# Sheet1.net
KiCad netlist of a schematic drawn in Altium Designer
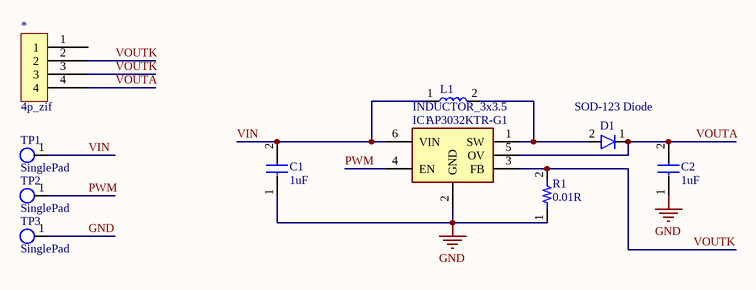
[diagram p0: Sheet1.SchDoc]

(export (version "E")
  (design (tool "Eeschema 10.0.6"))
  (components
    (comp (ref "*")
      (value "4p_zif")
      (footprint "4p_smd_zif")
      (libsource (lib "CONNECTORS AND MODULES") (part "4p_zif"))
    )
    (comp (ref "C1")
      (value "1uF")
      (footprint "0603 Capacitor")
      (description "Capacitor")
      (fields
        (field (name "MANUFACTURER_PART_NUMBER") "06031A120JAT2A")
        (field (name "MOUSER PART NUMBER") "581-06031A120J")
      )
      (libsource (lib "PASSIVE COMPONENTS") (part "0603 Capacitor"))
    )
    (comp (ref "C2")
      (value "1uF")
      (footprint "0603 Capacitor")
      (description "Capacitor")
      (fields
        (field (name "MANUFACTURER_PART_NUMBER") "06031A120JAT2A")
        (field (name "MOUSER PART NUMBER") "581-06031A120J")
      )
      (libsource (lib "PASSIVE COMPONENTS") (part "0603 Capacitor"))
    )
    (comp (ref "D1")
      (value "SOD-123 Diode")
      (footprint "SOD123")
      (description "Diode")
      (fields
        (field (name "MANUFACTURER_PART_NUMBER") "1N4148W-G3-08")
        (field (name "MOUSER PART NUMBER") "78-1N4148W-G3-08")
      )
      (libsource (lib "Schlib2") (part "SOD-123 Diode"))
    )
    (comp (ref "IC1")
      (value "AP3032KTR-G1")
      (footprint "PcbLib1:SOT95P280X145-6N")
      (description "Integrated Circuit")
      (fields (field (name "MOUSER PART NUMBER") "621-AP3032KTR-G1"))
      (libsource (lib "Schlib1") (part "AP3032KTR-G1"))
    )
    (comp (ref "L1")
      (value "INDUCTOR_3x3.5")
      (footprint "INDUCTOR_3x3.5")
      (description "Inductor")
      (fields (field (name "MANUFACTURER_PART_NUMBER") "CD32-4R7M"))
      (libsource (lib "PASSIVE COMPONENTS") (part "INDUCTOR_3x3.5"))
    )
    (comp (ref "R1")
      (value "0.01R")
      (footprint "0603 Resistor")
      (description "Resistor")
      (fields
        (field (name "MANUFACTURER_PART_NUMBER") "CPF0603B100RE1")
        (field (name "MOUSER PART NUMBER") "279-CPF0603B100RE1")
      )
      (libsource (lib "PASSIVE COMPONENTS") (part "0603 Resistor"))
    )
    (comp (ref "TP1")
      (value "SinglePad")
      (footprint "SinglePad1")
      (libsource (lib "PASSIVE COMPONENTS") (part "SinglePad"))
    )
    (comp (ref "TP2")
      (value "SinglePad")
      (footprint "SinglePad1")
      (libsource (lib "PASSIVE COMPONENTS") (part "SinglePad"))
    )
    (comp (ref "TP3")
      (value "SinglePad")
      (footprint "SinglePad1")
      (libsource (lib "PASSIVE COMPONENTS") (part "SinglePad"))
    )
  )
  (nets
    (net (code "1") (name "/PWM") (class "Default")
      (node (ref "IC1") (pin "4") (pinfunction "EN_4") (pintype "passive"))
      (node (ref "TP2") (pin "1") (pinfunction "1_1") (pintype "passive"))
    )
    (net (code "2") (name "/VIN") (class "Default")
      (node (ref "C1") (pin "2") (pinfunction "2_2") (pintype "passive"))
      (node (ref "IC1") (pin "6") (pinfunction "VIN_6") (pintype "passive"))
      (node (ref "L1") (pin "1") (pinfunction "1_1") (pintype "passive"))
      (node (ref "TP1") (pin "1") (pinfunction "1_1") (pintype "passive"))
    )
    (net (code "3") (name "/VOUTA") (class "Default")
      (node (ref "*") (pin "4") (pinfunction "4_4") (pintype "passive"))
      (node (ref "C2") (pin "2") (pinfunction "2_2") (pintype "passive"))
      (node (ref "D1") (pin "1") (pinfunction "K_1") (pintype "passive"))
      (node (ref "IC1") (pin "5") (pinfunction "OV_5") (pintype "passive"))
    )
    (net (code "4") (name "/VOUTK") (class "Default")
      (node (ref "*") (pin "2") (pinfunction "2_2") (pintype "passive"))
      (node (ref "*") (pin "3") (pinfunction "3_3") (pintype "passive"))
      (node (ref "IC1") (pin "3") (pinfunction "FB_3") (pintype "passive"))
      (node (ref "R1") (pin "2") (pinfunction "2_2") (pintype "passive"))
    )
    (net (code "5") (name "GND") (class "Default")
      (node (ref "C1") (pin "1") (pinfunction "1_1") (pintype "passive"))
      (node (ref "C2") (pin "1") (pinfunction "1_1") (pintype "passive"))
      (node (ref "IC1") (pin "2") (pinfunction "GND_2") (pintype "passive"))
      (node (ref "R1") (pin "1") (pinfunction "1_1") (pintype "passive"))
      (node (ref "TP3") (pin "1") (pinfunction "1_1") (pintype "passive"))
    )
    (net (code "6") (name "Net-(D1-A)") (class "Default")
      (node (ref "D1") (pin "2") (pinfunction "A_2") (pintype "passive"))
      (node (ref "IC1") (pin "1") (pinfunction "SW_1") (pintype "passive"))
      (node (ref "L1") (pin "2") (pinfunction "2_2") (pintype "passive"))
    )
    (net (code "7") (name "unconnected-(*-Pad1)") (class "Default")
      (node (ref "*") (pin "1") (pinfunction "1_1") (pintype "passive"))
    )
  )
)
